# usb_program_circuit.net
KiCad netlist of a schematic drawn in Altium Designer
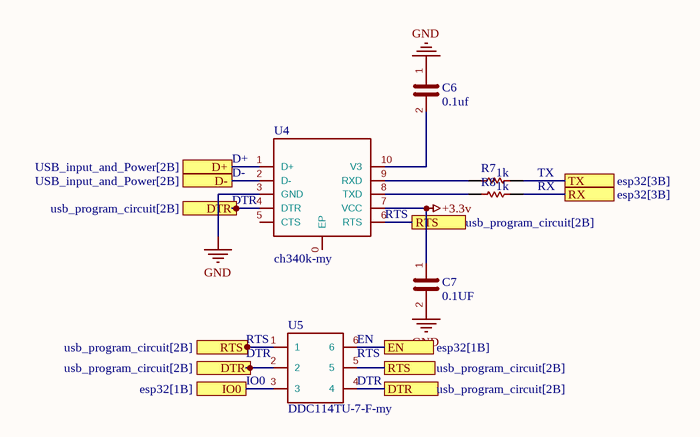
[diagram p0: usb_program_circuit.SchDoc]

(export (version "E")
  (design (tool "Eeschema 10.0.6"))
  (components
    (comp (ref "C6")
      (value "0.1uf")
      (footprint "CAPC2013X70X45NL10T25")
      (libsource (lib "Thermal_Camera") (part "C"))
    )
    (comp (ref "C7")
      (value "0.1UF")
      (footprint "CAPC2013X70X45NL10T25")
      (libsource (lib "Thermal_Camera") (part "C"))
    )
    (comp (ref "R7")
      (value "1k")
      (footprint "RESC2013X70X40NL20T20")
      (description "Chip Resistor, 1 KOhm, +/- 1%, 125 mW, -55 to 155 degC, 0805 (2012 Metric), RoHS, Tape and Reel")
      (fields (field (name "TOLERANCE") "1%") (field (name "MANUFACTURER") "Yageo"))
      (libsource (lib "Thermal_Camera") (part "CMP-2100-03671-1"))
    )
    (comp (ref "R8")
      (value "1k")
      (footprint "RESC2013X70X40NL20T20")
      (description "Chip Resistor, 1 KOhm, +/- 1%, 125 mW, -55 to 155 degC, 0805 (2012 Metric), RoHS, Tape and Reel")
      (fields (field (name "TOLERANCE") "1%") (field (name "MANUFACTURER") "Yageo"))
      (libsource (lib "Thermal_Camera") (part "CMP-2100-03671-1"))
    )
    (comp (ref "U4")
      (value "ch340k-my")
      (footprint "SOP100P600X160-11N")
      (libsource (lib "Thermal_Camera") (part "ch340k-my"))
    )
    (comp (ref "U5")
      (value "DDC114TU-7-F-my")
      (footprint "DDC114TU-7-F")
      (libsource (lib "Thermal_Camera") (part "DDC114TU-7-F-my"))
    )
  )
  (nets
    (net (code "1") (name "+3.3v") (class "Default")
      (node (ref "C7") (pin "1") (pinfunction "1_1") (pintype "passive"))
      (node (ref "U4") (pin "7") (pinfunction "VCC_7") (pintype "passive"))
    )
    (net (code "2") (name "/D+") (class "Default")
      (node (ref "U4") (pin "1") (pinfunction "D+_1") (pintype "passive"))
    )
    (net (code "3") (name "/D-") (class "Default")
      (node (ref "U4") (pin "2") (pinfunction "D-_2") (pintype "passive"))
    )
    (net (code "4") (name "/DTR") (class "Default")
      (node (ref "U4") (pin "4") (pinfunction "DTR_4") (pintype "passive"))
      (node (ref "U5") (pin "2") (pinfunction "2_2") (pintype "passive"))
      (node (ref "U5") (pin "4") (pinfunction "4_4") (pintype "passive"))
    )
    (net (code "5") (name "/EN") (class "Default")
      (node (ref "U5") (pin "6") (pinfunction "6_6") (pintype "passive"))
    )
    (net (code "6") (name "/IO0") (class "Default")
      (node (ref "U5") (pin "3") (pinfunction "3_3") (pintype "passive"))
    )
    (net (code "7") (name "/RTS") (class "Default")
      (node (ref "U4") (pin "6") (pinfunction "RTS_6") (pintype "passive"))
      (node (ref "U5") (pin "1") (pinfunction "1_1") (pintype "passive"))
      (node (ref "U5") (pin "5") (pinfunction "5_5") (pintype "passive"))
    )
    (net (code "8") (name "/RX") (class "Default")
      (node (ref "R8") (pin "1") (pinfunction "1_1") (pintype "passive"))
    )
    (net (code "9") (name "/TX") (class "Default")
      (node (ref "R7") (pin "1") (pinfunction "1_1") (pintype "passive"))
    )
    (net (code "10") (name "GND") (class "Default")
      (node (ref "C6") (pin "1") (pinfunction "1_1") (pintype "passive"))
      (node (ref "C7") (pin "2") (pinfunction "2_2") (pintype "passive"))
      (node (ref "U4") (pin "3") (pinfunction "GND_3") (pintype "passive"))
    )
    (net (code "11") (name "Net-(U4-RXD)") (class "Default")
      (node (ref "R7") (pin "2") (pinfunction "2_2") (pintype "passive"))
      (node (ref "U4") (pin "9") (pinfunction "RXD_9") (pintype "passive"))
    )
    (net (code "12") (name "Net-(U4-TXD)") (class "Default")
      (node (ref "R8") (pin "2") (pinfunction "2_2") (pintype "passive"))
      (node (ref "U4") (pin "8") (pinfunction "TXD_8") (pintype "passive"))
    )
    (net (code "13") (name "Net-(U4-V3)") (class "Default")
      (node (ref "C6") (pin "2") (pinfunction "2_2") (pintype "passive"))
      (node (ref "U4") (pin "10") (pinfunction "V3_10") (pintype "passive"))
    )
    (net (code "14") (name "unconnected-(U4-CTS-Pad5)") (class "Default")
      (node (ref "U4") (pin "5") (pinfunction "CTS_5") (pintype "passive"))
    )
    (net (code "15") (name "unconnected-(U4-EP-Pad0)") (class "Default")
      (node (ref "U4") (pin "0") (pinfunction "EP_0") (pintype "passive"))
    )
  )
)
